# line-following-car.net
KiCad netlist of a schematic drawn in EAGLE
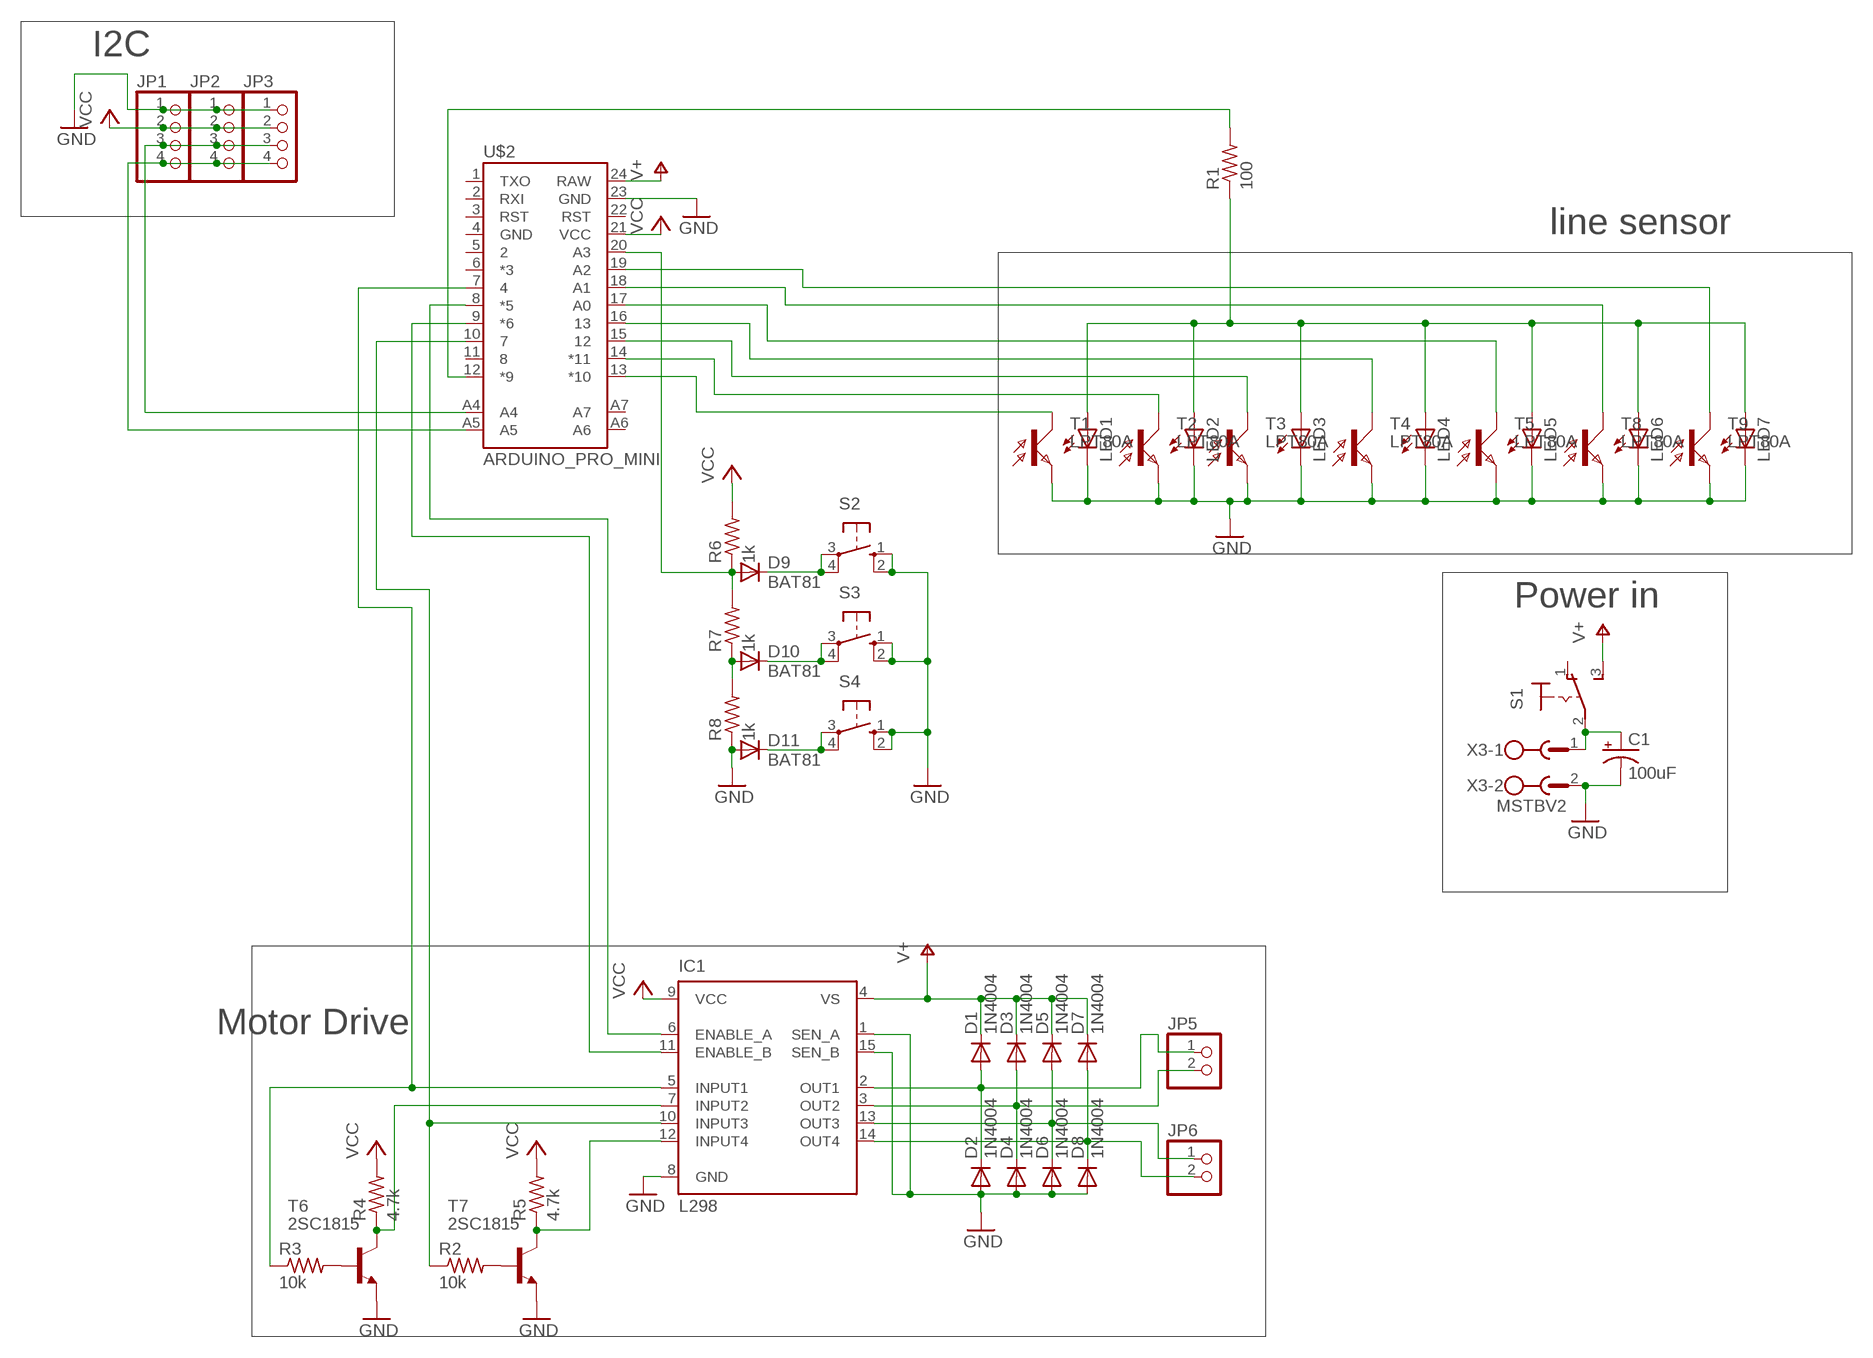
[diagram p0: schematic, sheet 1]

(export (version "E")
  (design (tool "Eeschema 10.0.6"))
  (components
    (comp (ref "C1")
      (value "100uF")
      (footprint "eagle-import:E2-4")
      (libsource (lib "eagle-import") (part "CPOL-USE2-4"))
    )
    (comp (ref "D1")
      (value "1N4004")
      (footprint "eagle-import:DO41-10")
      (libsource (lib "eagle-import") (part "1N4004"))
    )
    (comp (ref "D2")
      (value "1N4004")
      (footprint "eagle-import:DO41-10")
      (libsource (lib "eagle-import") (part "1N4004"))
    )
    (comp (ref "D3")
      (value "1N4004")
      (footprint "eagle-import:DO41-10")
      (libsource (lib "eagle-import") (part "1N4004"))
    )
    (comp (ref "D4")
      (value "1N4004")
      (footprint "eagle-import:DO41-10")
      (libsource (lib "eagle-import") (part "1N4004"))
    )
    (comp (ref "D5")
      (value "1N4004")
      (footprint "eagle-import:DO41-10")
      (libsource (lib "eagle-import") (part "1N4004"))
    )
    (comp (ref "D6")
      (value "1N4004")
      (footprint "eagle-import:DO41-10")
      (libsource (lib "eagle-import") (part "1N4004"))
    )
    (comp (ref "D7")
      (value "1N4004")
      (footprint "eagle-import:DO41-10")
      (libsource (lib "eagle-import") (part "1N4004"))
    )
    (comp (ref "D8")
      (value "1N4004")
      (footprint "eagle-import:DO41-10")
      (libsource (lib "eagle-import") (part "1N4004"))
    )
    (comp (ref "D9")
      (value "BAT81")
      (footprint "eagle-import:DO34-7")
      (libsource (lib "eagle-import") (part "BAT81"))
    )
    (comp (ref "D10")
      (value "BAT81")
      (footprint "eagle-import:DO34-7")
      (libsource (lib "eagle-import") (part "BAT81"))
    )
    (comp (ref "D11")
      (value "BAT81")
      (footprint "eagle-import:DO34-7")
      (libsource (lib "eagle-import") (part "BAT81"))
    )
    (comp (ref "IC1")
      (value "L298")
      (footprint "eagle-import:MULTIWATT-15")
      (fields (field (name "MPN") "L298N"))
      (libsource (lib "eagle-import") (part "L298"))
    )
    (comp (ref "JP1")
      (value "PINHD-1X4")
      (footprint "eagle-import:1X04")
      (libsource (lib "eagle-import") (part "PINHD-1X4"))
    )
    (comp (ref "JP2")
      (value "PINHD-1X4")
      (footprint "eagle-import:1X04")
      (libsource (lib "eagle-import") (part "PINHD-1X4"))
    )
    (comp (ref "JP3")
      (value "PINHD-1X4")
      (footprint "eagle-import:1X04")
      (libsource (lib "eagle-import") (part "PINHD-1X4"))
    )
    (comp (ref "JP5")
      (value "PINHD-1X2")
      (footprint "eagle-import:1X02")
      (libsource (lib "eagle-import") (part "PINHD-1X2"))
    )
    (comp (ref "JP6")
      (value "PINHD-1X2")
      (footprint "eagle-import:1X02")
      (libsource (lib "eagle-import") (part "PINHD-1X2"))
    )
    (comp (ref "LED1")
      (value "LED3MM")
      (footprint "eagle-import:LED3MM")
      (libsource (lib "eagle-import") (part "LED3MM"))
    )
    (comp (ref "LED2")
      (value "LED3MM")
      (footprint "eagle-import:LED3MM")
      (libsource (lib "eagle-import") (part "LED3MM"))
    )
    (comp (ref "LED3")
      (value "LED3MM")
      (footprint "eagle-import:LED3MM")
      (libsource (lib "eagle-import") (part "LED3MM"))
    )
    (comp (ref "LED4")
      (value "LED3MM")
      (footprint "eagle-import:LED3MM")
      (libsource (lib "eagle-import") (part "LED3MM"))
    )
    (comp (ref "LED5")
      (value "LED3MM")
      (footprint "eagle-import:LED3MM")
      (libsource (lib "eagle-import") (part "LED3MM"))
    )
    (comp (ref "LED6")
      (value "LED3MM")
      (footprint "eagle-import:LED3MM")
      (libsource (lib "eagle-import") (part "LED3MM"))
    )
    (comp (ref "LED7")
      (value "LED3MM")
      (footprint "eagle-import:LED3MM")
      (libsource (lib "eagle-import") (part "LED3MM"))
    )
    (comp (ref "R1")
      (value "100")
      (footprint "eagle-import:0204_5")
      (libsource (lib "eagle-import") (part "R-US_0204/5"))
    )
    (comp (ref "R2")
      (value "10k")
      (footprint "eagle-import:0204_5")
      (libsource (lib "eagle-import") (part "R-US_0204/5"))
    )
    (comp (ref "R3")
      (value "10k")
      (footprint "eagle-import:0204_5")
      (libsource (lib "eagle-import") (part "R-US_0204/5"))
    )
    (comp (ref "R4")
      (value "4.7k")
      (footprint "eagle-import:0204_5")
      (libsource (lib "eagle-import") (part "R-US_0204/5"))
    )
    (comp (ref "R5")
      (value "4.7k")
      (footprint "eagle-import:0204_5")
      (libsource (lib "eagle-import") (part "R-US_0204/5"))
    )
    (comp (ref "R6")
      (value "1k")
      (footprint "eagle-import:0207_7")
      (libsource (lib "eagle-import") (part "R-US_0207/7"))
    )
    (comp (ref "R7")
      (value "1k")
      (footprint "eagle-import:0207_7")
      (libsource (lib "eagle-import") (part "R-US_0207/7"))
    )
    (comp (ref "R8")
      (value "1k")
      (footprint "eagle-import:0207_7")
      (libsource (lib "eagle-import") (part "R-US_0207/7"))
    )
    (comp (ref "S1")
      (value "320-916")
      (footprint "eagle-import:320-916")
      (libsource (lib "eagle-import") (part "320-916"))
    )
    (comp (ref "S2")
      (value "10-XX")
      (footprint "eagle-import:B3F-10XX")
      (fields (field (name "MPN") "B3F-1000"))
      (libsource (lib "eagle-import") (part "10-XX"))
    )
    (comp (ref "S3")
      (value "10-XX")
      (footprint "eagle-import:B3F-10XX")
      (fields (field (name "MPN") "B3F-1000"))
      (libsource (lib "eagle-import") (part "10-XX"))
    )
    (comp (ref "S4")
      (value "10-XX")
      (footprint "eagle-import:B3F-10XX")
      (fields (field (name "MPN") "B3F-1000"))
      (libsource (lib "eagle-import") (part "10-XX"))
    )
    (comp (ref "T1")
      (value "LPT80A")
      (footprint "eagle-import:LPT80A")
      (libsource (lib "eagle-import") (part "LPT80A"))
    )
    (comp (ref "T2")
      (value "LPT80A")
      (footprint "eagle-import:LPT80A")
      (libsource (lib "eagle-import") (part "LPT80A"))
    )
    (comp (ref "T3")
      (value "LPT80A")
      (footprint "eagle-import:LPT80A")
      (libsource (lib "eagle-import") (part "LPT80A"))
    )
    (comp (ref "T4")
      (value "LPT80A")
      (footprint "eagle-import:LPT80A")
      (libsource (lib "eagle-import") (part "LPT80A"))
    )
    (comp (ref "T5")
      (value "LPT80A")
      (footprint "eagle-import:LPT80A")
      (libsource (lib "eagle-import") (part "LPT80A"))
    )
    (comp (ref "T6")
      (value "2SC1815")
      (footprint "eagle-import:TO92-ECB")
      (libsource (lib "eagle-import") (part "2SC1815"))
    )
    (comp (ref "T7")
      (value "2SC1815")
      (footprint "eagle-import:TO92-ECB")
      (libsource (lib "eagle-import") (part "2SC1815"))
    )
    (comp (ref "T8")
      (value "LPT80A")
      (footprint "eagle-import:LPT80A")
      (libsource (lib "eagle-import") (part "LPT80A"))
    )
    (comp (ref "T9")
      (value "LPT80A")
      (footprint "eagle-import:LPT80A")
      (libsource (lib "eagle-import") (part "LPT80A"))
    )
    (comp (ref "U$2")
      (value "ARDUINO_PRO_MINI")
      (footprint "eagle-import:ARDUINO_PRO_MINI")
      (libsource (lib "eagle-import") (part "ARDUINO_PRO_MINI"))
    )
    (comp (ref "X3")
      (value "MSTBV2")
      (footprint "eagle-import:MSTBV2")
      (fields (field (name "MPN") "MSTBV 2,5/2-GF-5.08"))
      (libsource (lib "eagle-import") (part "MSTBV2"))
    )
  )
  (nets
    (net (code "1") (name "GND") (class "Default")
      (node (ref "C1") (pin "-") (pinfunction "-_-") (pintype "passive"))
      (node (ref "D11") (pin "A") (pinfunction "A_A") (pintype "passive"))
      (node (ref "D2") (pin "A") (pinfunction "A_A") (pintype "passive"))
      (node (ref "D4") (pin "A") (pinfunction "A_A") (pintype "passive"))
      (node (ref "D6") (pin "A") (pinfunction "A_A") (pintype "passive"))
      (node (ref "D8") (pin "A") (pinfunction "A_A") (pintype "passive"))
      (node (ref "IC1") (pin "1") (pinfunction "SEN_A_1") (pintype "input"))
      (node (ref "IC1") (pin "15") (pinfunction "SEN_B_15") (pintype "input"))
      (node (ref "IC1") (pin "8") (pinfunction "GND_8") (pintype "power_in"))
      (node (ref "JP1") (pin "1") (pinfunction "1_1") (pintype "passive"))
      (node (ref "JP2") (pin "1") (pinfunction "1_1") (pintype "passive"))
      (node (ref "JP3") (pin "1") (pinfunction "1_1") (pintype "passive"))
      (node (ref "LED1") (pin "K") (pinfunction "C_K") (pintype "passive"))
      (node (ref "LED2") (pin "K") (pinfunction "C_K") (pintype "passive"))
      (node (ref "LED3") (pin "K") (pinfunction "C_K") (pintype "passive"))
      (node (ref "LED4") (pin "K") (pinfunction "C_K") (pintype "passive"))
      (node (ref "LED5") (pin "K") (pinfunction "C_K") (pintype "passive"))
      (node (ref "LED6") (pin "K") (pinfunction "C_K") (pintype "passive"))
      (node (ref "LED7") (pin "K") (pinfunction "C_K") (pintype "passive"))
      (node (ref "R8") (pin "1") (pinfunction "1_1") (pintype "passive"))
      (node (ref "S2") (pin "1") (pinfunction "S_1") (pintype "passive"))
      (node (ref "S2") (pin "2") (pinfunction "S1_2") (pintype "passive"))
      (node (ref "S3") (pin "1") (pinfunction "S_1") (pintype "passive"))
      (node (ref "S3") (pin "2") (pinfunction "S1_2") (pintype "passive"))
      (node (ref "S4") (pin "1") (pinfunction "S_1") (pintype "passive"))
      (node (ref "S4") (pin "2") (pinfunction "S1_2") (pintype "passive"))
      (node (ref "T1") (pin "E") (pinfunction "E_E") (pintype "passive"))
      (node (ref "T2") (pin "E") (pinfunction "E_E") (pintype "passive"))
      (node (ref "T3") (pin "E") (pinfunction "E_E") (pintype "passive"))
      (node (ref "T4") (pin "E") (pinfunction "E_E") (pintype "passive"))
      (node (ref "T5") (pin "E") (pinfunction "E_E") (pintype "passive"))
      (node (ref "T6") (pin "E") (pinfunction "E_E") (pintype "passive"))
      (node (ref "T7") (pin "E") (pinfunction "E_E") (pintype "passive"))
      (node (ref "T8") (pin "E") (pinfunction "E_E") (pintype "passive"))
      (node (ref "T9") (pin "E") (pinfunction "E_E") (pintype "passive"))
      (node (ref "U$2") (pin "23") (pinfunction "GND_23") (pintype "bidirectional"))
      (node (ref "X3") (pin "2") (pinfunction "1_2") (pintype "passive"))
    )
    (net (code "2") (name "Net-(D10-PadA)") (class "Default")
      (node (ref "D10") (pin "A") (pinfunction "A_A") (pintype "passive"))
      (node (ref "R7") (pin "1") (pinfunction "1_1") (pintype "passive"))
      (node (ref "R8") (pin "2") (pinfunction "2_2") (pintype "passive"))
    )
    (net (code "3") (name "Net-(IC1-ENABLE_A)") (class "Default")
      (node (ref "IC1") (pin "6") (pinfunction "ENABLE_A_6") (pintype "input"))
      (node (ref "U$2") (pin "8") (pinfunction "*5_8") (pintype "bidirectional"))
    )
    (net (code "4") (name "Net-(IC1-ENABLE_B)") (class "Default")
      (node (ref "IC1") (pin "11") (pinfunction "ENABLE_B_11") (pintype "input"))
      (node (ref "U$2") (pin "9") (pinfunction "*6_9") (pintype "bidirectional"))
    )
    (net (code "5") (name "Net-(IC1-INPUT1)") (class "Default")
      (node (ref "IC1") (pin "5") (pinfunction "INPUT1_5") (pintype "input"))
      (node (ref "R3") (pin "1") (pinfunction "1_1") (pintype "passive"))
      (node (ref "U$2") (pin "7") (pinfunction "4_7") (pintype "bidirectional"))
    )
    (net (code "6") (name "Net-(IC1-INPUT2)") (class "Default")
      (node (ref "IC1") (pin "7") (pinfunction "INPUT2_7") (pintype "input"))
      (node (ref "R4") (pin "1") (pinfunction "1_1") (pintype "passive"))
      (node (ref "T6") (pin "C") (pinfunction "C_C") (pintype "passive"))
    )
    (net (code "7") (name "Net-(IC1-INPUT3)") (class "Default")
      (node (ref "IC1") (pin "10") (pinfunction "INPUT3_10") (pintype "input"))
      (node (ref "R2") (pin "1") (pinfunction "1_1") (pintype "passive"))
      (node (ref "U$2") (pin "10") (pinfunction "7_10") (pintype "bidirectional"))
    )
    (net (code "8") (name "Net-(IC1-INPUT4)") (class "Default")
      (node (ref "IC1") (pin "12") (pinfunction "INPUT4_12") (pintype "input"))
      (node (ref "R5") (pin "1") (pinfunction "1_1") (pintype "passive"))
      (node (ref "T7") (pin "C") (pinfunction "C_C") (pintype "passive"))
    )
    (net (code "9") (name "Net-(IC1-OUT1)") (class "Default")
      (node (ref "D1") (pin "A") (pinfunction "A_A") (pintype "passive"))
      (node (ref "D2") (pin "C") (pinfunction "C_C") (pintype "passive"))
      (node (ref "IC1") (pin "2") (pinfunction "OUT1_2") (pintype "output"))
      (node (ref "JP5") (pin "1") (pinfunction "1_1") (pintype "passive"))
    )
    (net (code "10") (name "Net-(IC1-OUT2)") (class "Default")
      (node (ref "D3") (pin "A") (pinfunction "A_A") (pintype "passive"))
      (node (ref "D4") (pin "C") (pinfunction "C_C") (pintype "passive"))
      (node (ref "IC1") (pin "3") (pinfunction "OUT2_3") (pintype "output"))
      (node (ref "JP5") (pin "2") (pinfunction "2_2") (pintype "passive"))
    )
    (net (code "11") (name "Net-(IC1-OUT3)") (class "Default")
      (node (ref "D5") (pin "A") (pinfunction "A_A") (pintype "passive"))
      (node (ref "D6") (pin "C") (pinfunction "C_C") (pintype "passive"))
      (node (ref "IC1") (pin "13") (pinfunction "OUT3_13") (pintype "output"))
      (node (ref "JP6") (pin "1") (pinfunction "1_1") (pintype "passive"))
    )
    (net (code "12") (name "Net-(IC1-OUT4)") (class "Default")
      (node (ref "D7") (pin "A") (pinfunction "A_A") (pintype "passive"))
      (node (ref "D8") (pin "C") (pinfunction "C_C") (pintype "passive"))
      (node (ref "IC1") (pin "14") (pinfunction "OUT4_14") (pintype "output"))
      (node (ref "JP6") (pin "2") (pinfunction "2_2") (pintype "passive"))
    )
    (net (code "13") (name "Net-(JP1-Pad3)") (class "Default")
      (node (ref "JP1") (pin "3") (pinfunction "3_3") (pintype "passive"))
      (node (ref "JP2") (pin "3") (pinfunction "3_3") (pintype "passive"))
      (node (ref "JP3") (pin "3") (pinfunction "3_3") (pintype "passive"))
      (node (ref "U$2") (pin "A4") (pinfunction "A4_A4") (pintype "bidirectional"))
    )
    (net (code "14") (name "Net-(JP1-Pad4)") (class "Default")
      (node (ref "JP1") (pin "4") (pinfunction "4_4") (pintype "passive"))
      (node (ref "JP2") (pin "4") (pinfunction "4_4") (pintype "passive"))
      (node (ref "JP3") (pin "4") (pinfunction "4_4") (pintype "passive"))
      (node (ref "U$2") (pin "A5") (pinfunction "A5_A5") (pintype "bidirectional"))
    )
    (net (code "15") (name "Net-(LED1-PadA)") (class "Default")
      (node (ref "LED1") (pin "A") (pinfunction "A_A") (pintype "passive"))
      (node (ref "LED2") (pin "A") (pinfunction "A_A") (pintype "passive"))
      (node (ref "LED3") (pin "A") (pinfunction "A_A") (pintype "passive"))
      (node (ref "LED4") (pin "A") (pinfunction "A_A") (pintype "passive"))
      (node (ref "LED5") (pin "A") (pinfunction "A_A") (pintype "passive"))
      (node (ref "LED6") (pin "A") (pinfunction "A_A") (pintype "passive"))
      (node (ref "LED7") (pin "A") (pinfunction "A_A") (pintype "passive"))
      (node (ref "R1") (pin "1") (pinfunction "1_1") (pintype "passive"))
    )
    (net (code "16") (name "Net-(R2-Pad2)") (class "Default")
      (node (ref "R2") (pin "2") (pinfunction "2_2") (pintype "passive"))
      (node (ref "T7") (pin "B") (pinfunction "B_B") (pintype "passive"))
    )
    (net (code "17") (name "Net-(R3-Pad2)") (class "Default")
      (node (ref "R3") (pin "2") (pinfunction "2_2") (pintype "passive"))
      (node (ref "T6") (pin "B") (pinfunction "B_B") (pintype "passive"))
    )
    (net (code "18") (name "Net-(S1-P)") (class "Default")
      (node (ref "C1") (pin "+") (pinfunction "+_+") (pintype "passive"))
      (node (ref "S1") (pin "2") (pinfunction "P_2") (pintype "passive"))
      (node (ref "X3") (pin "1") (pinfunction "1_1") (pintype "passive"))
    )
    (net (code "19") (name "Net-(S2-P)") (class "Default")
      (node (ref "D9") (pin "C") (pinfunction "C_C") (pintype "passive"))
      (node (ref "S2") (pin "3") (pinfunction "P_3") (pintype "passive"))
      (node (ref "S2") (pin "4") (pinfunction "P1_4") (pintype "passive"))
    )
    (net (code "20") (name "Net-(S3-P)") (class "Default")
      (node (ref "D10") (pin "C") (pinfunction "C_C") (pintype "passive"))
      (node (ref "S3") (pin "3") (pinfunction "P_3") (pintype "passive"))
      (node (ref "S3") (pin "4") (pinfunction "P1_4") (pintype "passive"))
    )
    (net (code "21") (name "Net-(S4-P)") (class "Default")
      (node (ref "D11") (pin "C") (pinfunction "C_C") (pintype "passive"))
      (node (ref "S4") (pin "3") (pinfunction "P_3") (pintype "passive"))
      (node (ref "S4") (pin "4") (pinfunction "P1_4") (pintype "passive"))
    )
    (net (code "22") (name "Net-(U$2-*9)") (class "Default")
      (node (ref "R1") (pin "2") (pinfunction "2_2") (pintype "passive"))
      (node (ref "U$2") (pin "12") (pinfunction "*9_12") (pintype "bidirectional"))
    )
    (net (code "23") (name "Net-(U$2-*10)") (class "Default")
      (node (ref "T1") (pin "C") (pinfunction "C_C") (pintype "passive"))
      (node (ref "U$2") (pin "13") (pinfunction "*10_13") (pintype "bidirectional"))
    )
    (net (code "24") (name "Net-(U$2-*11)") (class "Default")
      (node (ref "T2") (pin "C") (pinfunction "C_C") (pintype "passive"))
      (node (ref "U$2") (pin "14") (pinfunction "*11_14") (pintype "bidirectional"))
    )
    (net (code "25") (name "Net-(U$2-12)") (class "Default")
      (node (ref "T3") (pin "C") (pinfunction "C_C") (pintype "passive"))
      (node (ref "U$2") (pin "15") (pinfunction "12_15") (pintype "bidirectional"))
    )
    (net (code "26") (name "Net-(U$2-13)") (class "Default")
      (node (ref "T4") (pin "C") (pinfunction "C_C") (pintype "passive"))
      (node (ref "U$2") (pin "16") (pinfunction "13_16") (pintype "bidirectional"))
    )
    (net (code "27") (name "Net-(U$2-A0)") (class "Default")
      (node (ref "T5") (pin "C") (pinfunction "C_C") (pintype "passive"))
      (node (ref "U$2") (pin "17") (pinfunction "A0_17") (pintype "bidirectional"))
    )
    (net (code "28") (name "Net-(U$2-A1)") (class "Default")
      (node (ref "T8") (pin "C") (pinfunction "C_C") (pintype "passive"))
      (node (ref "U$2") (pin "18") (pinfunction "A1_18") (pintype "bidirectional"))
    )
    (net (code "29") (name "Net-(U$2-A2)") (class "Default")
      (node (ref "T9") (pin "C") (pinfunction "C_C") (pintype "passive"))
      (node (ref "U$2") (pin "19") (pinfunction "A2_19") (pintype "bidirectional"))
    )
    (net (code "30") (name "Net-(U$2-A3)") (class "Default")
      (node (ref "D9") (pin "A") (pinfunction "A_A") (pintype "passive"))
      (node (ref "R6") (pin "1") (pinfunction "1_1") (pintype "passive"))
      (node (ref "R7") (pin "2") (pinfunction "2_2") (pintype "passive"))
      (node (ref "U$2") (pin "20") (pinfunction "A3_20") (pintype "bidirectional"))
    )
    (net (code "31") (name "V+") (class "Default")
      (node (ref "D1") (pin "C") (pinfunction "C_C") (pintype "passive"))
      (node (ref "D3") (pin "C") (pinfunction "C_C") (pintype "passive"))
      (node (ref "D5") (pin "C") (pinfunction "C_C") (pintype "passive"))
      (node (ref "D7") (pin "C") (pinfunction "C_C") (pintype "passive"))
      (node (ref "IC1") (pin "4") (pinfunction "VS_4") (pintype "power_in"))
      (node (ref "S1") (pin "3") (pinfunction "S_3") (pintype "passive"))
      (node (ref "U$2") (pin "24") (pinfunction "RAW_24") (pintype "bidirectional"))
    )
    (net (code "32") (name "VCC") (class "Default")
      (node (ref "IC1") (pin "9") (pinfunction "VCC_9") (pintype "power_in"))
      (node (ref "JP1") (pin "2") (pinfunction "2_2") (pintype "passive"))
      (node (ref "JP2") (pin "2") (pinfunction "2_2") (pintype "passive"))
      (node (ref "JP3") (pin "2") (pinfunction "2_2") (pintype "passive"))
      (node (ref "R4") (pin "2") (pinfunction "2_2") (pintype "passive"))
      (node (ref "R5") (pin "2") (pinfunction "2_2") (pintype "passive"))
      (node (ref "R6") (pin "2") (pinfunction "2_2") (pintype "passive"))
      (node (ref "U$2") (pin "21") (pinfunction "VCC_21") (pintype "bidirectional"))
    )
    (net (code "33") (name "unconnected-(S1-O-Pad1)") (class "Default")
      (node (ref "S1") (pin "1") (pinfunction "O_1") (pintype "passive"))
    )
    (net (code "34") (name "unconnected-(U$2-*3-Pad6)") (class "Default")
      (node (ref "U$2") (pin "6") (pinfunction "*3_6") (pintype "bidirectional"))
    )
    (net (code "35") (name "unconnected-(U$2-2-Pad5)") (class "Default")
      (node (ref "U$2") (pin "5") (pinfunction "2_5") (pintype "bidirectional"))
    )
    (net (code "36") (name "unconnected-(U$2-8-Pad11)") (class "Default")
      (node (ref "U$2") (pin "11") (pinfunction "8_11") (pintype "bidirectional"))
    )
    (net (code "37") (name "unconnected-(U$2-GND-Pad4)") (class "Default")
      (node (ref "U$2") (pin "4") (pinfunction "GND_4") (pintype "bidirectional"))
    )
    (net (code "38") (name "unconnected-(U$2-PadA6)") (class "Default")
      (node (ref "U$2") (pin "A6") (pinfunction "A6_A6") (pintype "bidirectional"))
    )
    (net (code "39") (name "unconnected-(U$2-PadA7)") (class "Default")
      (node (ref "U$2") (pin "A7") (pinfunction "A7_A7") (pintype "bidirectional"))
    )
    (net (code "40") (name "unconnected-(U$2-RST-Pad3)") (class "Default")
      (node (ref "U$2") (pin "3") (pinfunction "RST_3") (pintype "bidirectional"))
    )
    (net (code "41") (name "unconnected-(U$2-RST-Pad22)") (class "Default")
      (node (ref "U$2") (pin "22") (pinfunction "RST_22") (pintype "bidirectional"))
    )
    (net (code "42") (name "unconnected-(U$2-RXI-Pad2)") (class "Default")
      (node (ref "U$2") (pin "2") (pinfunction "RXI_2") (pintype "bidirectional"))
    )
    (net (code "43") (name "unconnected-(U$2-TXO-Pad1)") (class "Default")
      (node (ref "U$2") (pin "1") (pinfunction "TXO_1") (pintype "bidirectional"))
    )
  )
)
